# Sheet1.net
KiCad netlist of a schematic drawn in Altium Designer
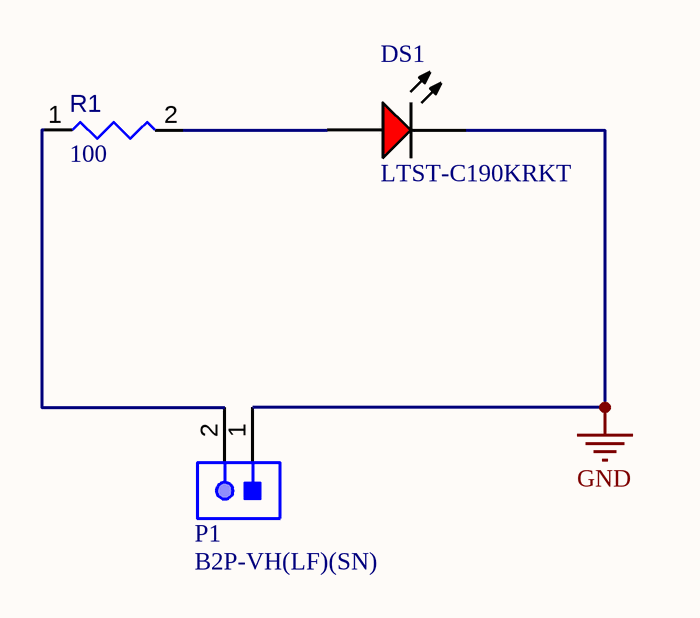
[diagram p0: Sheet1.SchDoc]

(export (version "E")
  (design (tool "Eeschema 10.0.6"))
  (components
    (comp (ref "DS1")
      (value "LTST-C190KRKT")
      (footprint "LTST-C191KRKT_V")
      (description "LED Uni-Color Red, 62.5 mW, 25 mA, -30 to 85 degC, 2-Pin SMD, RoHS, Tape and Reel")
      (fields (field (name "POWER") "75mW") (field (name "MANUFACTURER") "Lite-On"))
      (libsource (lib "Ufscar - Universidade Federal de São Carlos") (part "LED-RED-AK-2"))
    )
    (comp (ref "P1")
      (value "B2P-VH(LF)(SN)")
      (footprint "JST-B2P-VH(LF)(SN)_V")
      (fields (field (name "MANUFACTURER") "JST"))
      (libsource (lib "Ufscar - Universidade Federal de São Carlos") (part "CN-1P-M-R2"))
    )
    (comp (ref "R1")
      (value "100")
      (footprint "RESC0402(1005)_L")
      (description "Chip Resistor, 100 Ohms, +/-1 %, 63 mW, -55 to 155 degC, 0402")
      (fields (field (name "POWER") "63mW") (field (name "TOLERANCE") "1%"))
      (libsource (lib "Ufscar - Universidade Federal de São Carlos") (part "RES-2"))
    )
  )
  (nets
    (net (code "1") (name "GND") (class "Default")
      (node (ref "DS1") (pin "2") (pinfunction "K_2") (pintype "passive"))
      (node (ref "P1") (pin "1") (pinfunction "1_1") (pintype "passive"))
    )
    (net (code "2") (name "Net-(DS1-A)") (class "Default")
      (node (ref "DS1") (pin "1") (pinfunction "A_1") (pintype "passive"))
      (node (ref "R1") (pin "2") (pinfunction "2_2") (pintype "passive"))
    )
    (net (code "3") (name "Net-(P1-Pad2)") (class "Default")
      (node (ref "P1") (pin "2") (pinfunction "2_2") (pintype "passive"))
      (node (ref "R1") (pin "1") (pinfunction "1_1") (pintype "passive"))
    )
  )
)
